# Connectors.net
KiCad netlist of a schematic drawn in Altium Designer
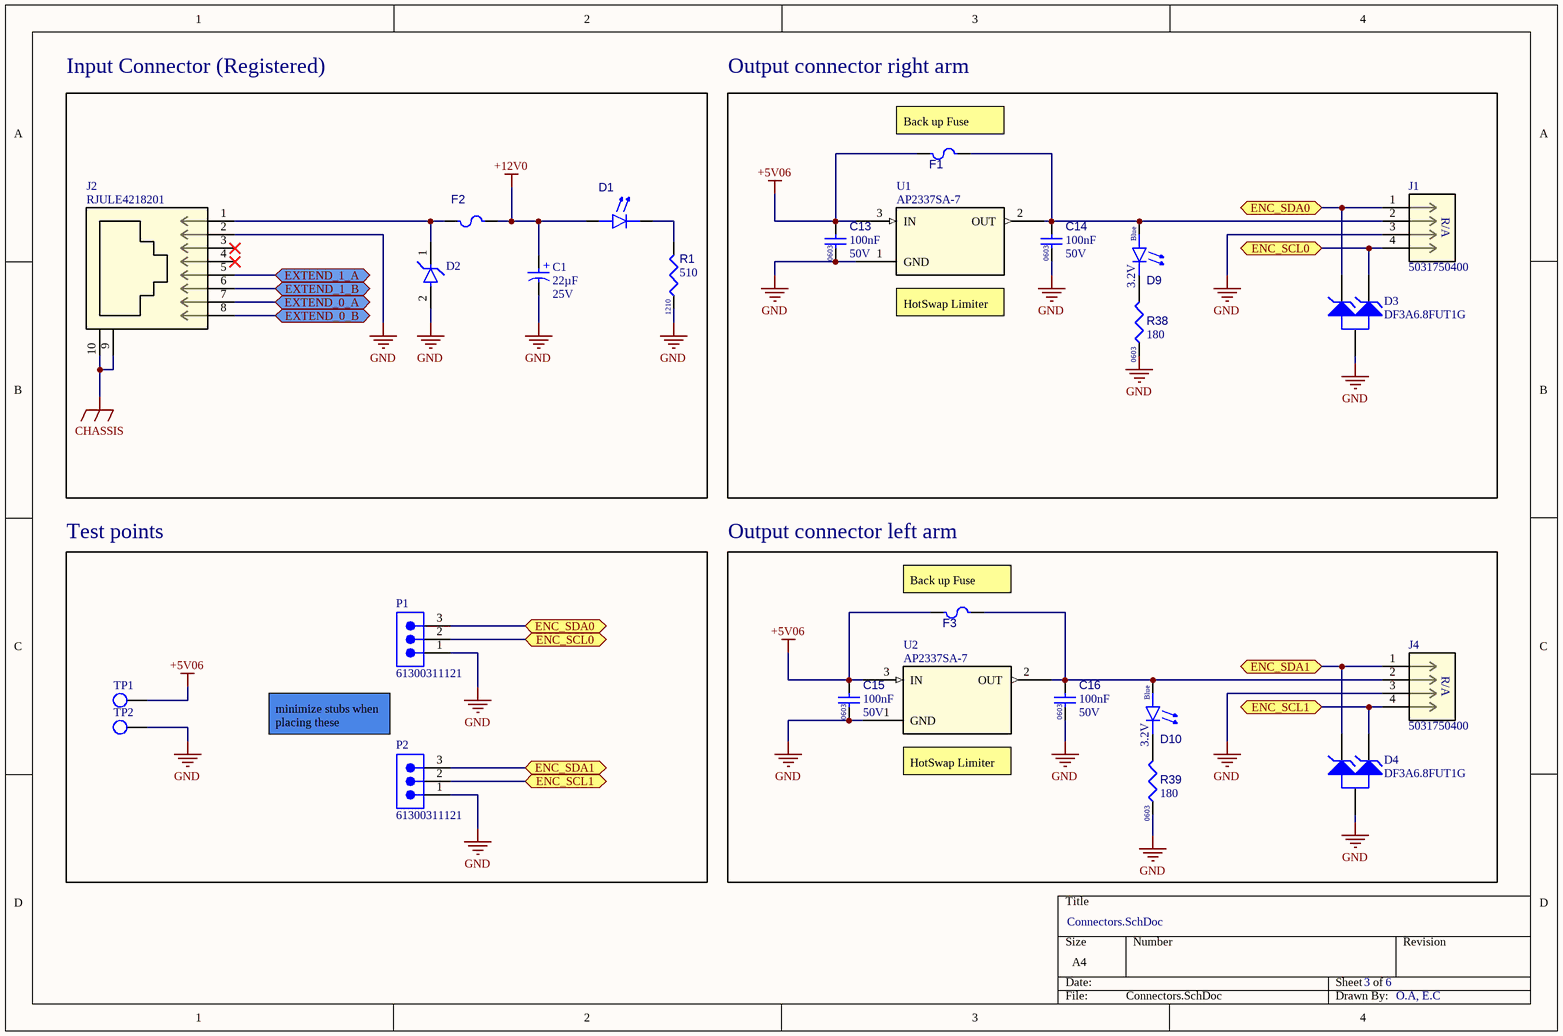
[diagram p0: Connectors.SchDoc]

(export (version "E")
  (design (tool "Eeschema 10.0.6"))
  (components
    (comp (ref "C1")
      (value "22µF")
      (footprint "WCAP-PSLP_D6.3H5.8")
      (description "22 µF 25 V Aluminum - Polymer Capacitors Radial, Can - SMD 30mOhm 2000 Hrs @ 105°C")
      (fields
        (field (name "TOLERANCE") "20%")
        (field (name "VOLTAGE RATING") "25V")
        (field (name "Comment") "875105544003")
      )
      (libsource (lib "hawaiirobotics") (part "Capacitor_Polarized"))
    )
    (comp (ref "C13")
      (value "100nF")
      (footprint "CAPC1608X90X40NL10T20")
      (description "Chip Capacitor, 100 nF, +/- 10%, 50 V, 0603 (1608 Metric)")
      (fields
        (field (name "TOLERANCE") "10%")
        (field (name "VOLTAGE RATING") "50V")
        (field (name "CASE/PACKAGE") "0603")
        (field (name "Comment") "Capacitor 100 nF +/-10% 50 V 0603")
      )
      (libsource (lib "hawaiirobotics") (part "CAP-NP-2"))
    )
    (comp (ref "C14")
      (value "100nF")
      (footprint "CAPC1608X90X40NL10T20")
      (description "Chip Capacitor, 100 nF, +/- 10%, 50 V, 0603 (1608 Metric)")
      (fields
        (field (name "TOLERANCE") "10%")
        (field (name "VOLTAGE RATING") "50V")
        (field (name "CASE/PACKAGE") "0603")
        (field (name "Comment") "Capacitor 100 nF +/-10% 50 V 0603")
      )
      (libsource (lib "hawaiirobotics") (part "CAP-NP-2"))
    )
    (comp (ref "C15")
      (value "100nF")
      (footprint "CAPC1608X90X40NL10T20")
      (description "Chip Capacitor, 100 nF, +/- 10%, 50 V, 0603 (1608 Metric)")
      (fields
        (field (name "TOLERANCE") "10%")
        (field (name "VOLTAGE RATING") "50V")
        (field (name "CASE/PACKAGE") "0603")
        (field (name "Comment") "Capacitor 100 nF +/-10% 50 V 0603")
      )
      (libsource (lib "hawaiirobotics") (part "CAP-NP-2"))
    )
    (comp (ref "C16")
      (value "100nF")
      (footprint "CAPC1608X90X40NL10T20")
      (description "Chip Capacitor, 100 nF, +/- 10%, 50 V, 0603 (1608 Metric)")
      (fields
        (field (name "TOLERANCE") "10%")
        (field (name "VOLTAGE RATING") "50V")
        (field (name "CASE/PACKAGE") "0603")
        (field (name "Comment") "Capacitor 100 nF +/-10% 50 V 0603")
      )
      (libsource (lib "hawaiirobotics") (part "CAP-NP-2"))
    )
    (comp (ref "D1")
      (value "150060RS75000")
      (footprint "WL-SMCW_0603_150060xx75000")
      (description "Single Color LED, Red, Water Clear, 1.1mm")
      (libsource (lib "hawaiirobotics") (part "DIODE-LED-2"))
    )
    (comp (ref "D2")
      (value "SMAJ5.0A-13-F")
      (footprint "FP-SMA-MFG")
      (description "Trans Voltage Suppressor Diode, 400W, 5V V(RWM), Unidirectional, 1 Element, Silicon")
      (libsource (lib "hawaiirobotics") (part "f813f71cba58e380607f5dd3caf9714"))
    )
    (comp (ref "D3")
      (value "DF3A6.8FUT1G")
      (footprint "ONSC-SC-70-3-419-04_V")
      (description "Trans Voltage Suppressor Diode, 150W, Unidirectional, 2 Element, Silicon")
      (libsource (lib "hawaiirobotics") (part "ONSC-K1K2A3-3"))
    )
    (comp (ref "D4")
      (value "DF3A6.8FUT1G")
      (footprint "ONSC-SC-70-3-419-04_V")
      (description "Trans Voltage Suppressor Diode, 150W, Unidirectional, 2 Element, Silicon")
      (libsource (lib "hawaiirobotics") (part "ONSC-K1K2A3-3"))
    )
    (comp (ref "D9")
      (value "150060BS75000")
      (footprint "WL-SMCW_0603_150060xx75000")
      (description "Single Color LED, Blue, Water Clear, 1.1mm")
      (fields (field (name "NOMINAL VF") "3.2V") (field (name "COLOR") "Blue"))
      (libsource (lib "hawaiirobotics") (part "DIODE-LED-2"))
    )
    (comp (ref "D10")
      (value "150060BS75000")
      (footprint "WL-SMCW_0603_150060xx75000")
      (description "Single Color LED, Blue, Water Clear, 1.1mm")
      (fields (field (name "NOMINAL VF") "3.2V") (field (name "COLOR") "Blue"))
      (libsource (lib "hawaiirobotics") (part "DIODE-LED-2"))
    )
    (comp (ref "F1")
      (value "MF-PSMF050X-2")
      (footprint "FP-MF-PSMF-MFG")
      (description "PTC Resettable Fuse, 6V, Surface Mount")
      (fields (field (name "POWER") "500mW"))
      (libsource (lib "hawaiirobotics") (part "FUSE-2"))
    )
    (comp (ref "F2")
      (value "MF-MSMF075-2")
      (footprint "BOUR-MF-MSMF050-2_V")
      (description "PTC Resettable Fuse, 13.2V, Surface Mount")
      (fields (field (name "POWER") "800mW"))
      (libsource (lib "hawaiirobotics") (part "FUSE-2"))
    )
    (comp (ref "F3")
      (value "MF-PSMF050X-2")
      (footprint "FP-MF-PSMF-MFG")
      (description "PTC Resettable Fuse, 6V, Surface Mount")
      (fields (field (name "POWER") "500mW"))
      (libsource (lib "hawaiirobotics") (part "FUSE-2"))
    )
    (comp (ref "J1")
      (value "5031750400")
      (footprint "5031750400-Footprint-1")
      (libsource (lib "hawaiirobotics") (part "5031750400-Symbol-1"))
    )
    (comp (ref "J2")
      (value "RJULE4218201")
      (footprint "RJULE4218201-Footprint-1")
      (description "Modular Jack - Right Angle, Input Output Connectors RJ45, 8P8C, Without LEDs, Shield.")
      (libsource (lib "hawaiirobotics") (part "RJULE4218201-Symbol-1"))
    )
    (comp (ref "J4")
      (value "5031750400")
      (footprint "5031750400-Footprint-1")
      (libsource (lib "hawaiirobotics") (part "5031750400-Symbol-1"))
    )
    (comp (ref "P1")
      (value "61300311121")
      (footprint "61300311121")
      (libsource (lib "hawaiirobotics") (part "Header_Male_1R_03P"))
    )
    (comp (ref "P2")
      (value "61300311121")
      (footprint "61300311121")
      (libsource (lib "hawaiirobotics") (part "Header_Male_1R_03P"))
    )
    (comp (ref "R1")
      (value "510")
      (footprint "RESC3126X60X50NL10T20")
      (fields
        (field (name "CASE/PACKAGE") "1210")
        (field (name "POWER") "500mW")
        (field (name "TOLERANCE") "5%")
        (field (name "Comment") "RC1210JR-07510RL")
      )
      (libsource (lib "hawaiirobotics") (part "RES-2"))
    )
    (comp (ref "R38")
      (value "180")
      (footprint "RESC0603(1608)_N")
      (fields
        (field (name "TOLERANCE") "5%")
        (field (name "CASE/PACKAGE") "0603")
        (field (name "POWER") "100mW")
        (field (name "Comment") "RC0603JR-07180RL")
      )
      (libsource (lib "hawaiirobotics") (part "RES-2"))
    )
    (comp (ref "R39")
      (value "180")
      (footprint "RESC0603(1608)_N")
      (fields
        (field (name "TOLERANCE") "5%")
        (field (name "CASE/PACKAGE") "0603")
        (field (name "POWER") "100mW")
        (field (name "Comment") "RC0603JR-07180RL")
      )
      (libsource (lib "hawaiirobotics") (part "RES-2"))
    )
    (comp (ref "TP1")
      (value "RCUCTE")
      (footprint "FP-S2761-46R-MFG")
      (description "Test point")
      (libsource (lib "hawaiirobotics") (part "RCUCTE-Symbol-1"))
    )
    (comp (ref "TP2")
      (value "RCUCTE")
      (footprint "FP-S2761-46R-MFG")
      (description "Test point")
      (libsource (lib "hawaiirobotics") (part "RCUCTE-Symbol-1"))
    )
    (comp (ref "U1")
      (value "AP2337SA-7")
      (footprint "SOT90P240X120-3L")
      (description "Power Supply Support Circuit, Fixed, 1 Channel, PDSO3")
      (libsource (lib "hawaiirobotics") (part "AP2337SA-7-Symbol-1"))
    )
    (comp (ref "U2")
      (value "AP2337SA-7")
      (footprint "SOT90P240X120-3L")
      (description "Power Supply Support Circuit, Fixed, 1 Channel, PDSO3")
      (libsource (lib "hawaiirobotics") (part "AP2337SA-7-Symbol-1"))
    )
  )
  (nets
    (net (code "1") (name "+5V06") (class "Default")
      (node (ref "C13") (pin "2") (pinfunction "2_2") (pintype "passive"))
      (node (ref "C15") (pin "2") (pinfunction "2_2") (pintype "passive"))
      (node (ref "F1") (pin "2") (pinfunction "2_2") (pintype "passive"))
      (node (ref "F3") (pin "2") (pinfunction "2_2") (pintype "passive"))
      (node (ref "TP1") (pin "1") (pinfunction "1_1") (pintype "passive"))
      (node (ref "U1") (pin "3") (pinfunction "IN_3") (pintype "input"))
      (node (ref "U2") (pin "3") (pinfunction "IN_3") (pintype "input"))
    )
    (net (code "2") (name "+12V0") (class "Default")
      (node (ref "C1") (pin "1") (pinfunction "P_1") (pintype "passive"))
      (node (ref "D1") (pin "2") (pinfunction "A_2") (pintype "passive"))
      (node (ref "F2") (pin "2") (pinfunction "2_2") (pintype "passive"))
    )
    (net (code "3") (name "/ENC_SCL0") (class "Default")
      (node (ref "D3") (pin "2") (pinfunction "K2_2") (pintype "passive"))
      (node (ref "J1") (pin "4") (pinfunction "4_4") (pintype "passive"))
      (node (ref "P1") (pin "2") (pinfunction "2_2") (pintype "passive"))
    )
    (net (code "4") (name "/ENC_SCL1") (class "Default")
      (node (ref "D4") (pin "2") (pinfunction "K2_2") (pintype "passive"))
      (node (ref "J4") (pin "4") (pinfunction "4_4") (pintype "passive"))
      (node (ref "P2") (pin "2") (pinfunction "2_2") (pintype "passive"))
    )
    (net (code "5") (name "/ENC_SDA0") (class "Default")
      (node (ref "D3") (pin "1") (pinfunction "K1_1") (pintype "passive"))
      (node (ref "J1") (pin "1") (pinfunction "1_1") (pintype "passive"))
      (node (ref "P1") (pin "3") (pinfunction "3_3") (pintype "passive"))
    )
    (net (code "6") (name "/ENC_SDA1") (class "Default")
      (node (ref "D4") (pin "1") (pinfunction "K1_1") (pintype "passive"))
      (node (ref "J4") (pin "1") (pinfunction "1_1") (pintype "passive"))
      (node (ref "P2") (pin "3") (pinfunction "3_3") (pintype "passive"))
    )
    (net (code "7") (name "/EXTEND_0_A") (class "Default")
      (node (ref "J2") (pin "7") (pinfunction "7_7") (pintype "passive"))
    )
    (net (code "8") (name "/EXTEND_0_B") (class "Default")
      (node (ref "J2") (pin "8") (pinfunction "8_8") (pintype "passive"))
    )
    (net (code "9") (name "/EXTEND_1_A") (class "Default")
      (node (ref "J2") (pin "5") (pinfunction "5_5") (pintype "passive"))
    )
    (net (code "10") (name "/EXTEND_1_B") (class "Default")
      (node (ref "J2") (pin "6") (pinfunction "6_6") (pintype "passive"))
    )
    (net (code "11") (name "CHASSIS") (class "Default")
      (node (ref "J2") (pin "10") (pinfunction "10_10") (pintype "passive"))
      (node (ref "J2") (pin "9") (pinfunction "9_9") (pintype "passive"))
    )
    (net (code "12") (name "GND") (class "Default")
      (node (ref "C1") (pin "2") (pinfunction "N_2") (pintype "passive"))
      (node (ref "C13") (pin "1") (pinfunction "1_1") (pintype "passive"))
      (node (ref "C14") (pin "1") (pinfunction "1_1") (pintype "passive"))
      (node (ref "C15") (pin "1") (pinfunction "1_1") (pintype "passive"))
      (node (ref "C16") (pin "1") (pinfunction "1_1") (pintype "passive"))
      (node (ref "D2") (pin "2") (pinfunction "A_2") (pintype "passive"))
      (node (ref "D3") (pin "3") (pinfunction "A_3") (pintype "passive"))
      (node (ref "D4") (pin "3") (pinfunction "A_3") (pintype "passive"))
      (node (ref "J1") (pin "3") (pinfunction "3_3") (pintype "passive"))
      (node (ref "J2") (pin "2") (pinfunction "2_2") (pintype "passive"))
      (node (ref "J4") (pin "3") (pinfunction "3_3") (pintype "passive"))
      (node (ref "P1") (pin "1") (pinfunction "1_1") (pintype "passive"))
      (node (ref "P2") (pin "1") (pinfunction "1_1") (pintype "passive"))
      (node (ref "R1") (pin "1") (pinfunction "1_1") (pintype "passive"))
      (node (ref "R38") (pin "1") (pinfunction "1_1") (pintype "passive"))
      (node (ref "R39") (pin "1") (pinfunction "1_1") (pintype "passive"))
      (node (ref "TP2") (pin "1") (pinfunction "1_1") (pintype "passive"))
      (node (ref "U1") (pin "1") (pinfunction "GND_1") (pintype "power_in"))
      (node (ref "U2") (pin "1") (pinfunction "GND_1") (pintype "power_in"))
    )
    (net (code "13") (name "Net-(D1-K)") (class "Default")
      (node (ref "D1") (pin "1") (pinfunction "K_1") (pintype "passive"))
      (node (ref "R1") (pin "2") (pinfunction "2_2") (pintype "passive"))
    )
    (net (code "14") (name "Net-(D2-C)") (class "Default")
      (node (ref "D2") (pin "1") (pinfunction "C_1") (pintype "passive"))
      (node (ref "F2") (pin "1") (pinfunction "1_1") (pintype "passive"))
      (node (ref "J2") (pin "1") (pinfunction "1_1") (pintype "passive"))
    )
    (net (code "15") (name "Net-(D9-A)") (class "Default")
      (node (ref "C14") (pin "2") (pinfunction "2_2") (pintype "passive"))
      (node (ref "D9") (pin "2") (pinfunction "A_2") (pintype "passive"))
      (node (ref "F1") (pin "1") (pinfunction "1_1") (pintype "passive"))
      (node (ref "J1") (pin "2") (pinfunction "2_2") (pintype "passive"))
      (node (ref "U1") (pin "2") (pinfunction "OUT_2") (pintype "output"))
    )
    (net (code "16") (name "Net-(D9-K)") (class "Default")
      (node (ref "D9") (pin "1") (pinfunction "K_1") (pintype "passive"))
      (node (ref "R38") (pin "2") (pinfunction "2_2") (pintype "passive"))
    )
    (net (code "17") (name "Net-(D10-A)") (class "Default")
      (node (ref "C16") (pin "2") (pinfunction "2_2") (pintype "passive"))
      (node (ref "D10") (pin "2") (pinfunction "A_2") (pintype "passive"))
      (node (ref "F3") (pin "1") (pinfunction "1_1") (pintype "passive"))
      (node (ref "J4") (pin "2") (pinfunction "2_2") (pintype "passive"))
      (node (ref "U2") (pin "2") (pinfunction "OUT_2") (pintype "output"))
    )
    (net (code "18") (name "Net-(D10-K)") (class "Default")
      (node (ref "D10") (pin "1") (pinfunction "K_1") (pintype "passive"))
      (node (ref "R39") (pin "2") (pinfunction "2_2") (pintype "passive"))
    )
    (net (code "19") (name "unconnected-(J2-Pad3)") (class "Default")
      (node (ref "J2") (pin "3") (pinfunction "3_3") (pintype "passive+no_connect"))
    )
    (net (code "20") (name "unconnected-(J2-Pad4)") (class "Default")
      (node (ref "J2") (pin "4") (pinfunction "4_4") (pintype "passive+no_connect"))
    )
  )
)
